# Leds.net
KiCad netlist of a schematic drawn in Altium Designer
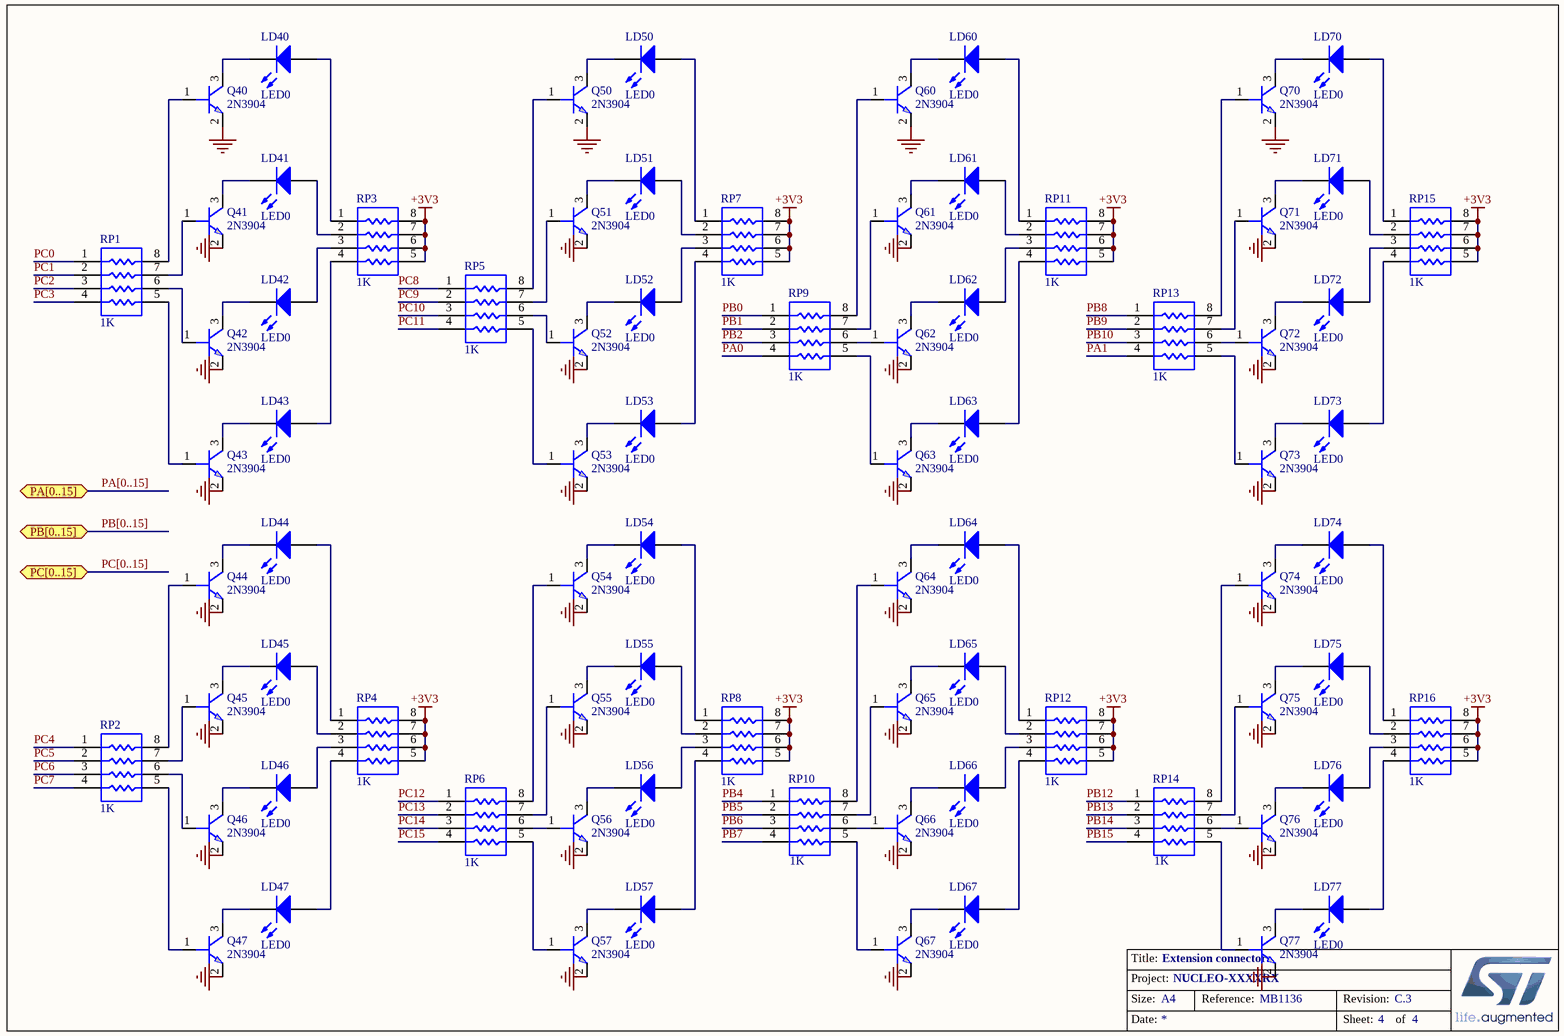
[diagram p0: Leds.SchDoc]

(export (version "E")
  (design (tool "Eeschema 10.0.6"))
  (components
    (comp (ref "LD40")
      (value "LED0")
      (footprint "LED5")
      (description "Typical INFRARED GaAs LED")
      (fields (field (name "PUBLISHER") "Altium Limited"))
      (libsource (lib "Miscellaneous Devices") (part "LED0"))
    )
    (comp (ref "LD41")
      (value "LED0")
      (footprint "LED5")
      (description "Typical INFRARED GaAs LED")
      (fields (field (name "PUBLISHER") "Altium Limited"))
      (libsource (lib "Miscellaneous Devices") (part "LED0"))
    )
    (comp (ref "LD42")
      (value "LED0")
      (footprint "LED5")
      (description "Typical INFRARED GaAs LED")
      (fields (field (name "PUBLISHER") "Altium Limited"))
      (libsource (lib "Miscellaneous Devices") (part "LED0"))
    )
    (comp (ref "LD43")
      (value "LED0")
      (footprint "LED5")
      (description "Typical INFRARED GaAs LED")
      (fields (field (name "PUBLISHER") "Altium Limited"))
      (libsource (lib "Miscellaneous Devices") (part "LED0"))
    )
    (comp (ref "LD44")
      (value "LED0")
      (footprint "LED5")
      (description "Typical INFRARED GaAs LED")
      (fields (field (name "PUBLISHER") "Altium Limited"))
      (libsource (lib "Miscellaneous Devices") (part "LED0"))
    )
    (comp (ref "LD45")
      (value "LED0")
      (footprint "LED5")
      (description "Typical INFRARED GaAs LED")
      (fields (field (name "PUBLISHER") "Altium Limited"))
      (libsource (lib "Miscellaneous Devices") (part "LED0"))
    )
    (comp (ref "LD46")
      (value "LED0")
      (footprint "LED5")
      (description "Typical INFRARED GaAs LED")
      (fields (field (name "PUBLISHER") "Altium Limited"))
      (libsource (lib "Miscellaneous Devices") (part "LED0"))
    )
    (comp (ref "LD47")
      (value "LED0")
      (footprint "LED5")
      (description "Typical INFRARED GaAs LED")
      (fields (field (name "PUBLISHER") "Altium Limited"))
      (libsource (lib "Miscellaneous Devices") (part "LED0"))
    )
    (comp (ref "LD50")
      (value "LED0")
      (footprint "LED5")
      (description "Typical INFRARED GaAs LED")
      (fields (field (name "PUBLISHER") "Altium Limited"))
      (libsource (lib "Miscellaneous Devices") (part "LED0"))
    )
    (comp (ref "LD51")
      (value "LED0")
      (footprint "LED5")
      (description "Typical INFRARED GaAs LED")
      (fields (field (name "PUBLISHER") "Altium Limited"))
      (libsource (lib "Miscellaneous Devices") (part "LED0"))
    )
    (comp (ref "LD52")
      (value "LED0")
      (footprint "LED5")
      (description "Typical INFRARED GaAs LED")
      (fields (field (name "PUBLISHER") "Altium Limited"))
      (libsource (lib "Miscellaneous Devices") (part "LED0"))
    )
    (comp (ref "LD53")
      (value "LED0")
      (footprint "LED5")
      (description "Typical INFRARED GaAs LED")
      (fields (field (name "PUBLISHER") "Altium Limited"))
      (libsource (lib "Miscellaneous Devices") (part "LED0"))
    )
    (comp (ref "LD54")
      (value "LED0")
      (footprint "LED5")
      (description "Typical INFRARED GaAs LED")
      (fields (field (name "PUBLISHER") "Altium Limited"))
      (libsource (lib "Miscellaneous Devices") (part "LED0"))
    )
    (comp (ref "LD55")
      (value "LED0")
      (footprint "LED5")
      (description "Typical INFRARED GaAs LED")
      (fields (field (name "PUBLISHER") "Altium Limited"))
      (libsource (lib "Miscellaneous Devices") (part "LED0"))
    )
    (comp (ref "LD56")
      (value "LED0")
      (footprint "LED5")
      (description "Typical INFRARED GaAs LED")
      (fields (field (name "PUBLISHER") "Altium Limited"))
      (libsource (lib "Miscellaneous Devices") (part "LED0"))
    )
    (comp (ref "LD57")
      (value "LED0")
      (footprint "LED5")
      (description "Typical INFRARED GaAs LED")
      (fields (field (name "PUBLISHER") "Altium Limited"))
      (libsource (lib "Miscellaneous Devices") (part "LED0"))
    )
    (comp (ref "LD60")
      (value "LED0")
      (footprint "LED5")
      (description "Typical INFRARED GaAs LED")
      (fields (field (name "PUBLISHER") "Altium Limited"))
      (libsource (lib "Miscellaneous Devices") (part "LED0"))
    )
    (comp (ref "LD61")
      (value "LED0")
      (footprint "LED5")
      (description "Typical INFRARED GaAs LED")
      (fields (field (name "PUBLISHER") "Altium Limited"))
      (libsource (lib "Miscellaneous Devices") (part "LED0"))
    )
    (comp (ref "LD62")
      (value "LED0")
      (footprint "LED5")
      (description "Typical INFRARED GaAs LED")
      (fields (field (name "PUBLISHER") "Altium Limited"))
      (libsource (lib "Miscellaneous Devices") (part "LED0"))
    )
    (comp (ref "LD63")
      (value "LED0")
      (footprint "LED5")
      (description "Typical INFRARED GaAs LED")
      (fields (field (name "PUBLISHER") "Altium Limited"))
      (libsource (lib "Miscellaneous Devices") (part "LED0"))
    )
    (comp (ref "LD64")
      (value "LED0")
      (footprint "LED5")
      (description "Typical INFRARED GaAs LED")
      (fields (field (name "PUBLISHER") "Altium Limited"))
      (libsource (lib "Miscellaneous Devices") (part "LED0"))
    )
    (comp (ref "LD65")
      (value "LED0")
      (footprint "LED5")
      (description "Typical INFRARED GaAs LED")
      (fields (field (name "PUBLISHER") "Altium Limited"))
      (libsource (lib "Miscellaneous Devices") (part "LED0"))
    )
    (comp (ref "LD66")
      (value "LED0")
      (footprint "LED5")
      (description "Typical INFRARED GaAs LED")
      (fields (field (name "PUBLISHER") "Altium Limited"))
      (libsource (lib "Miscellaneous Devices") (part "LED0"))
    )
    (comp (ref "LD67")
      (value "LED0")
      (footprint "LED5")
      (description "Typical INFRARED GaAs LED")
      (fields (field (name "PUBLISHER") "Altium Limited"))
      (libsource (lib "Miscellaneous Devices") (part "LED0"))
    )
    (comp (ref "LD70")
      (value "LED0")
      (footprint "LED5")
      (description "Typical INFRARED GaAs LED")
      (fields (field (name "PUBLISHER") "Altium Limited"))
      (libsource (lib "Miscellaneous Devices") (part "LED0"))
    )
    (comp (ref "LD71")
      (value "LED0")
      (footprint "LED5")
      (description "Typical INFRARED GaAs LED")
      (fields (field (name "PUBLISHER") "Altium Limited"))
      (libsource (lib "Miscellaneous Devices") (part "LED0"))
    )
    (comp (ref "LD72")
      (value "LED0")
      (footprint "LED5")
      (description "Typical INFRARED GaAs LED")
      (fields (field (name "PUBLISHER") "Altium Limited"))
      (libsource (lib "Miscellaneous Devices") (part "LED0"))
    )
    (comp (ref "LD73")
      (value "LED0")
      (footprint "LED5")
      (description "Typical INFRARED GaAs LED")
      (fields (field (name "PUBLISHER") "Altium Limited"))
      (libsource (lib "Miscellaneous Devices") (part "LED0"))
    )
    (comp (ref "LD74")
      (value "LED0")
      (footprint "LED5")
      (description "Typical INFRARED GaAs LED")
      (fields (field (name "PUBLISHER") "Altium Limited"))
      (libsource (lib "Miscellaneous Devices") (part "LED0"))
    )
    (comp (ref "LD75")
      (value "LED0")
      (footprint "LED5")
      (description "Typical INFRARED GaAs LED")
      (fields (field (name "PUBLISHER") "Altium Limited"))
      (libsource (lib "Miscellaneous Devices") (part "LED0"))
    )
    (comp (ref "LD76")
      (value "LED0")
      (footprint "LED5")
      (description "Typical INFRARED GaAs LED")
      (fields (field (name "PUBLISHER") "Altium Limited"))
      (libsource (lib "Miscellaneous Devices") (part "LED0"))
    )
    (comp (ref "LD77")
      (value "LED0")
      (footprint "LED5")
      (description "Typical INFRARED GaAs LED")
      (fields (field (name "PUBLISHER") "Altium Limited"))
      (libsource (lib "Miscellaneous Devices") (part "LED0"))
    )
    (comp (ref "Q40") (value "2N3904") (footprint "SOT-23") (libsource (lib "*") (part "2N5551")))
    (comp (ref "Q41") (value "2N3904") (footprint "SOT-23") (libsource (lib "*") (part "2N5551")))
    (comp (ref "Q42") (value "2N3904") (footprint "SOT-23") (libsource (lib "*") (part "2N5551")))
    (comp (ref "Q43") (value "2N3904") (footprint "SOT-23") (libsource (lib "*") (part "2N5551")))
    (comp (ref "Q44") (value "2N3904") (footprint "SOT-23") (libsource (lib "*") (part "2N5551")))
    (comp (ref "Q45") (value "2N3904") (footprint "SOT-23") (libsource (lib "*") (part "2N5551")))
    (comp (ref "Q46") (value "2N3904") (footprint "SOT-23") (libsource (lib "*") (part "2N5551")))
    (comp (ref "Q47") (value "2N3904") (footprint "SOT-23") (libsource (lib "*") (part "2N5551")))
    (comp (ref "Q50") (value "2N3904") (footprint "SOT-23") (libsource (lib "*") (part "2N5551")))
    (comp (ref "Q51") (value "2N3904") (footprint "SOT-23") (libsource (lib "*") (part "2N5551")))
    (comp (ref "Q52") (value "2N3904") (footprint "SOT-23") (libsource (lib "*") (part "2N5551")))
    (comp (ref "Q53") (value "2N3904") (footprint "SOT-23") (libsource (lib "*") (part "2N5551")))
    (comp (ref "Q54") (value "2N3904") (footprint "SOT-23") (libsource (lib "*") (part "2N5551")))
    (comp (ref "Q55") (value "2N3904") (footprint "SOT-23") (libsource (lib "*") (part "2N5551")))
    (comp (ref "Q56") (value "2N3904") (footprint "SOT-23") (libsource (lib "*") (part "2N5551")))
    (comp (ref "Q57") (value "2N3904") (footprint "SOT-23") (libsource (lib "*") (part "2N5551")))
    (comp (ref "Q60") (value "2N3904") (footprint "SOT-23") (libsource (lib "*") (part "2N5551")))
    (comp (ref "Q61") (value "2N3904") (footprint "SOT-23") (libsource (lib "*") (part "2N5551")))
    (comp (ref "Q62") (value "2N3904") (footprint "SOT-23") (libsource (lib "*") (part "2N5551")))
    (comp (ref "Q63") (value "2N3904") (footprint "SOT-23") (libsource (lib "*") (part "2N5551")))
    (comp (ref "Q64") (value "2N3904") (footprint "SOT-23") (libsource (lib "*") (part "2N5551")))
    (comp (ref "Q65") (value "2N3904") (footprint "SOT-23") (libsource (lib "*") (part "2N5551")))
    (comp (ref "Q66") (value "2N3904") (footprint "SOT-23") (libsource (lib "*") (part "2N5551")))
    (comp (ref "Q67") (value "2N3904") (footprint "SOT-23") (libsource (lib "*") (part "2N5551")))
    (comp (ref "Q70") (value "2N3904") (footprint "SOT-23") (libsource (lib "*") (part "2N5551")))
    (comp (ref "Q71") (value "2N3904") (footprint "SOT-23") (libsource (lib "*") (part "2N5551")))
    (comp (ref "Q72") (value "2N3904") (footprint "SOT-23") (libsource (lib "*") (part "2N5551")))
    (comp (ref "Q73") (value "2N3904") (footprint "SOT-23") (libsource (lib "*") (part "2N5551")))
    (comp (ref "Q74") (value "2N3904") (footprint "SOT-23") (libsource (lib "*") (part "2N5551")))
    (comp (ref "Q75") (value "2N3904") (footprint "SOT-23") (libsource (lib "*") (part "2N5551")))
    (comp (ref "Q76") (value "2N3904") (footprint "SOT-23") (libsource (lib "*") (part "2N5551")))
    (comp (ref "Q77") (value "2N3904") (footprint "SOT-23") (libsource (lib "*") (part "2N5551")))
    (comp (ref "RP1") (value "1K") (footprint "4P8") (libsource (lib "*") (part "RESPACK3_1")))
    (comp (ref "RP2") (value "1K") (footprint "4P8") (libsource (lib "*") (part "RESPACK3_1")))
    (comp (ref "RP3") (value "1K") (footprint "4P8") (libsource (lib "*") (part "RESPACK3_1")))
    (comp (ref "RP4") (value "1K") (footprint "4P8") (libsource (lib "*") (part "RESPACK3_1")))
    (comp (ref "RP5") (value "1K") (footprint "4P8") (libsource (lib "*") (part "RESPACK3_1")))
    (comp (ref "RP6") (value "1K") (footprint "4P8") (libsource (lib "*") (part "RESPACK3_1")))
    (comp (ref "RP7") (value "1K") (footprint "4P8") (libsource (lib "*") (part "RESPACK3_1")))
    (comp (ref "RP8") (value "1K") (footprint "4P8") (libsource (lib "*") (part "RESPACK3_1")))
    (comp (ref "RP9") (value "1K") (footprint "4P8") (libsource (lib "*") (part "RESPACK3_1")))
    (comp (ref "RP10") (value "1K") (footprint "4P8") (libsource (lib "*") (part "RESPACK3_1")))
    (comp (ref "RP11") (value "1K") (footprint "4P8") (libsource (lib "*") (part "RESPACK3_1")))
    (comp (ref "RP12") (value "1K") (footprint "4P8") (libsource (lib "*") (part "RESPACK3_1")))
    (comp (ref "RP13") (value "1K") (footprint "4P8") (libsource (lib "*") (part "RESPACK3_1")))
    (comp (ref "RP14") (value "1K") (footprint "4P8") (libsource (lib "*") (part "RESPACK3_1")))
    (comp (ref "RP15") (value "1K") (footprint "4P8") (libsource (lib "*") (part "RESPACK3_1")))
    (comp (ref "RP16") (value "1K") (footprint "4P8") (libsource (lib "*") (part "RESPACK3_1")))
  )
  (nets
    (net (code "17") (name "+3V3") (class "Default")
      (node (ref "RP11") (pin "5") (pinfunction "5_5") (pintype "passive"))
      (node (ref "RP11") (pin "6") (pinfunction "6_6") (pintype "passive"))
      (node (ref "RP11") (pin "7") (pinfunction "7_7") (pintype "passive"))
      (node (ref "RP11") (pin "8") (pinfunction "8_8") (pintype "passive"))
      (node (ref "RP12") (pin "5") (pinfunction "5_5") (pintype "passive"))
      (node (ref "RP12") (pin "6") (pinfunction "6_6") (pintype "passive"))
      (node (ref "RP12") (pin "7") (pinfunction "7_7") (pintype "passive"))
      (node (ref "RP12") (pin "8") (pinfunction "8_8") (pintype "passive"))
      (node (ref "RP15") (pin "5") (pinfunction "5_5") (pintype "passive"))
      (node (ref "RP15") (pin "6") (pinfunction "6_6") (pintype "passive"))
      (node (ref "RP15") (pin "7") (pinfunction "7_7") (pintype "passive"))
      (node (ref "RP15") (pin "8") (pinfunction "8_8") (pintype "passive"))
      (node (ref "RP16") (pin "5") (pinfunction "5_5") (pintype "passive"))
      (node (ref "RP16") (pin "6") (pinfunction "6_6") (pintype "passive"))
      (node (ref "RP16") (pin "7") (pinfunction "7_7") (pintype "passive"))
      (node (ref "RP16") (pin "8") (pinfunction "8_8") (pintype "passive"))
      (node (ref "RP3") (pin "5") (pinfunction "5_5") (pintype "passive"))
      (node (ref "RP3") (pin "6") (pinfunction "6_6") (pintype "passive"))
      (node (ref "RP3") (pin "7") (pinfunction "7_7") (pintype "passive"))
      (node (ref "RP3") (pin "8") (pinfunction "8_8") (pintype "passive"))
      (node (ref "RP4") (pin "5") (pinfunction "5_5") (pintype "passive"))
      (node (ref "RP4") (pin "6") (pinfunction "6_6") (pintype "passive"))
      (node (ref "RP4") (pin "7") (pinfunction "7_7") (pintype "passive"))
      (node (ref "RP4") (pin "8") (pinfunction "8_8") (pintype "passive"))
      (node (ref "RP7") (pin "5") (pinfunction "5_5") (pintype "passive"))
      (node (ref "RP7") (pin "6") (pinfunction "6_6") (pintype "passive"))
      (node (ref "RP7") (pin "7") (pinfunction "7_7") (pintype "passive"))
      (node (ref "RP7") (pin "8") (pinfunction "8_8") (pintype "passive"))
      (node (ref "RP8") (pin "5") (pinfunction "5_5") (pintype "passive"))
      (node (ref "RP8") (pin "6") (pinfunction "6_6") (pintype "passive"))
      (node (ref "RP8") (pin "7") (pinfunction "7_7") (pintype "passive"))
      (node (ref "RP8") (pin "8") (pinfunction "8_8") (pintype "passive"))
    )
    (net (code "18") (name "/PA0") (class "Default")
      (node (ref "RP9") (pin "4") (pinfunction "4_4") (pintype "passive"))
    )
    (net (code "19") (name "/PA1") (class "Default")
      (node (ref "RP13") (pin "4") (pinfunction "4_4") (pintype "passive"))
    )
    (net (code "21") (name "/PB0") (class "Default")
      (node (ref "RP9") (pin "1") (pinfunction "1_1") (pintype "passive"))
    )
    (net (code "22") (name "/PB1") (class "Default")
      (node (ref "RP9") (pin "2") (pinfunction "2_2") (pintype "passive"))
    )
    (net (code "23") (name "/PB2") (class "Default")
      (node (ref "RP9") (pin "3") (pinfunction "3_3") (pintype "passive"))
    )
    (net (code "24") (name "/PB4") (class "Default")
      (node (ref "RP10") (pin "1") (pinfunction "1_1") (pintype "passive"))
    )
    (net (code "25") (name "/PB5") (class "Default")
      (node (ref "RP10") (pin "2") (pinfunction "2_2") (pintype "passive"))
    )
    (net (code "26") (name "/PB6") (class "Default")
      (node (ref "RP10") (pin "3") (pinfunction "3_3") (pintype "passive"))
    )
    (net (code "27") (name "/PB7") (class "Default")
      (node (ref "RP10") (pin "4") (pinfunction "4_4") (pintype "passive"))
    )
    (net (code "28") (name "/PB8") (class "Default")
      (node (ref "RP13") (pin "1") (pinfunction "1_1") (pintype "passive"))
    )
    (net (code "29") (name "/PB9") (class "Default")
      (node (ref "RP13") (pin "2") (pinfunction "2_2") (pintype "passive"))
    )
    (net (code "30") (name "/PB10") (class "Default")
      (node (ref "RP13") (pin "3") (pinfunction "3_3") (pintype "passive"))
    )
    (net (code "31") (name "/PB12") (class "Default")
      (node (ref "RP14") (pin "1") (pinfunction "1_1") (pintype "passive"))
    )
    (net (code "32") (name "/PB13") (class "Default")
      (node (ref "RP14") (pin "2") (pinfunction "2_2") (pintype "passive"))
    )
    (net (code "33") (name "/PB14") (class "Default")
      (node (ref "RP14") (pin "3") (pinfunction "3_3") (pintype "passive"))
    )
    (net (code "34") (name "/PB15") (class "Default")
      (node (ref "RP14") (pin "4") (pinfunction "4_4") (pintype "passive"))
    )
    (net (code "36") (name "/PC0") (class "Default")
      (node (ref "RP1") (pin "1") (pinfunction "1_1") (pintype "passive"))
    )
    (net (code "37") (name "/PC1") (class "Default")
      (node (ref "RP1") (pin "2") (pinfunction "2_2") (pintype "passive"))
    )
    (net (code "38") (name "/PC2") (class "Default")
      (node (ref "RP1") (pin "3") (pinfunction "3_3") (pintype "passive"))
    )
    (net (code "39") (name "/PC3") (class "Default")
      (node (ref "RP1") (pin "4") (pinfunction "4_4") (pintype "passive"))
    )
    (net (code "40") (name "/PC4") (class "Default")
      (node (ref "RP2") (pin "1") (pinfunction "1_1") (pintype "passive"))
    )
    (net (code "41") (name "/PC5") (class "Default")
      (node (ref "RP2") (pin "2") (pinfunction "2_2") (pintype "passive"))
    )
    (net (code "42") (name "/PC6") (class "Default")
      (node (ref "RP2") (pin "3") (pinfunction "3_3") (pintype "passive"))
    )
    (net (code "43") (name "/PC7") (class "Default")
      (node (ref "RP2") (pin "4") (pinfunction "4_4") (pintype "passive"))
    )
    (net (code "44") (name "/PC8") (class "Default")
      (node (ref "RP5") (pin "1") (pinfunction "1_1") (pintype "passive"))
    )
    (net (code "45") (name "/PC9") (class "Default")
      (node (ref "RP5") (pin "2") (pinfunction "2_2") (pintype "passive"))
    )
    (net (code "46") (name "/PC10") (class "Default")
      (node (ref "RP5") (pin "3") (pinfunction "3_3") (pintype "passive"))
    )
    (net (code "47") (name "/PC11") (class "Default")
      (node (ref "RP5") (pin "4") (pinfunction "4_4") (pintype "passive"))
    )
    (net (code "48") (name "/PC12") (class "Default")
      (node (ref "RP6") (pin "1") (pinfunction "1_1") (pintype "passive"))
    )
    (net (code "49") (name "/PC13") (class "Default")
      (node (ref "RP6") (pin "2") (pinfunction "2_2") (pintype "passive"))
    )
    (net (code "50") (name "/PC14") (class "Default")
      (node (ref "RP6") (pin "3") (pinfunction "3_3") (pintype "passive"))
    )
    (net (code "51") (name "/PC15") (class "Default")
      (node (ref "RP6") (pin "4") (pinfunction "4_4") (pintype "passive"))
    )
    (net (code "53") (name "GND") (class "Default")
      (node (ref "Q40") (pin "2") (pinfunction "E_2") (pintype "passive"))
      (node (ref "Q41") (pin "2") (pinfunction "E_2") (pintype "passive"))
      (node (ref "Q42") (pin "2") (pinfunction "E_2") (pintype "passive"))
      (node (ref "Q43") (pin "2") (pinfunction "E_2") (pintype "passive"))
      (node (ref "Q44") (pin "2") (pinfunction "E_2") (pintype "passive"))
      (node (ref "Q45") (pin "2") (pinfunction "E_2") (pintype "passive"))
      (node (ref "Q46") (pin "2") (pinfunction "E_2") (pintype "passive"))
      (node (ref "Q47") (pin "2") (pinfunction "E_2") (pintype "passive"))
      (node (ref "Q50") (pin "2") (pinfunction "E_2") (pintype "passive"))
      (node (ref "Q51") (pin "2") (pinfunction "E_2") (pintype "passive"))
      (node (ref "Q52") (pin "2") (pinfunction "E_2") (pintype "passive"))
      (node (ref "Q53") (pin "2") (pinfunction "E_2") (pintype "passive"))
      (node (ref "Q54") (pin "2") (pinfunction "E_2") (pintype "passive"))
      (node (ref "Q55") (pin "2") (pinfunction "E_2") (pintype "passive"))
      (node (ref "Q56") (pin "2") (pinfunction "E_2") (pintype "passive"))
      (node (ref "Q57") (pin "2") (pinfunction "E_2") (pintype "passive"))
      (node (ref "Q60") (pin "2") (pinfunction "E_2") (pintype "passive"))
      (node (ref "Q61") (pin "2") (pinfunction "E_2") (pintype "passive"))
      (node (ref "Q62") (pin "2") (pinfunction "E_2") (pintype "passive"))
      (node (ref "Q63") (pin "2") (pinfunction "E_2") (pintype "passive"))
      (node (ref "Q64") (pin "2") (pinfunction "E_2") (pintype "passive"))
      (node (ref "Q65") (pin "2") (pinfunction "E_2") (pintype "passive"))
      (node (ref "Q66") (pin "2") (pinfunction "E_2") (pintype "passive"))
      (node (ref "Q67") (pin "2") (pinfunction "E_2") (pintype "passive"))
      (node (ref "Q70") (pin "2") (pinfunction "E_2") (pintype "passive"))
      (node (ref "Q71") (pin "2") (pinfunction "E_2") (pintype "passive"))
      (node (ref "Q72") (pin "2") (pinfunction "E_2") (pintype "passive"))
      (node (ref "Q73") (pin "2") (pinfunction "E_2") (pintype "passive"))
      (node (ref "Q74") (pin "2") (pinfunction "E_2") (pintype "passive"))
      (node (ref "Q75") (pin "2") (pinfunction "E_2") (pintype "passive"))
      (node (ref "Q76") (pin "2") (pinfunction "E_2") (pintype "passive"))
      (node (ref "Q77") (pin "2") (pinfunction "E_2") (pintype "passive"))
    )
    (net (code "54") (name "Net-(LD40-A)") (class "Default")
      (node (ref "LD40") (pin "1") (pinfunction "A_1") (pintype "passive"))
      (node (ref "RP3") (pin "1") (pinfunction "1_1") (pintype "passive"))
    )
    (net (code "55") (name "Net-(LD40-K)") (class "Default")
      (node (ref "LD40") (pin "2") (pinfunction "K_2") (pintype "passive"))
      (node (ref "Q40") (pin "3") (pinfunction "C_3") (pintype "passive"))
    )
    (net (code "56") (name "Net-(LD41-A)") (class "Default")
      (node (ref "LD41") (pin "1") (pinfunction "A_1") (pintype "passive"))
      (node (ref "RP3") (pin "2") (pinfunction "2_2") (pintype "passive"))
    )
    (net (code "57") (name "Net-(LD41-K)") (class "Default")
      (node (ref "LD41") (pin "2") (pinfunction "K_2") (pintype "passive"))
      (node (ref "Q41") (pin "3") (pinfunction "C_3") (pintype "passive"))
    )
    (net (code "58") (name "Net-(LD42-A)") (class "Default")
      (node (ref "LD42") (pin "1") (pinfunction "A_1") (pintype "passive"))
      (node (ref "RP3") (pin "3") (pinfunction "3_3") (pintype "passive"))
    )
    (net (code "59") (name "Net-(LD42-K)") (class "Default")
      (node (ref "LD42") (pin "2") (pinfunction "K_2") (pintype "passive"))
      (node (ref "Q42") (pin "3") (pinfunction "C_3") (pintype "passive"))
    )
    (net (code "60") (name "Net-(LD43-A)") (class "Default")
      (node (ref "LD43") (pin "1") (pinfunction "A_1") (pintype "passive"))
      (node (ref "RP3") (pin "4") (pinfunction "4_4") (pintype "passive"))
    )
    (net (code "61") (name "Net-(LD43-K)") (class "Default")
      (node (ref "LD43") (pin "2") (pinfunction "K_2") (pintype "passive"))
      (node (ref "Q43") (pin "3") (pinfunction "C_3") (pintype "passive"))
    )
    (net (code "62") (name "Net-(LD44-A)") (class "Default")
      (node (ref "LD44") (pin "1") (pinfunction "A_1") (pintype "passive"))
      (node (ref "RP4") (pin "1") (pinfunction "1_1") (pintype "passive"))
    )
    (net (code "63") (name "Net-(LD44-K)") (class "Default")
      (node (ref "LD44") (pin "2") (pinfunction "K_2") (pintype "passive"))
      (node (ref "Q44") (pin "3") (pinfunction "C_3") (pintype "passive"))
    )
    (net (code "64") (name "Net-(LD45-A)") (class "Default")
      (node (ref "LD45") (pin "1") (pinfunction "A_1") (pintype "passive"))
      (node (ref "RP4") (pin "2") (pinfunction "2_2") (pintype "passive"))
    )
    (net (code "65") (name "Net-(LD45-K)") (class "Default")
      (node (ref "LD45") (pin "2") (pinfunction "K_2") (pintype "passive"))
      (node (ref "Q45") (pin "3") (pinfunction "C_3") (pintype "passive"))
    )
    (net (code "66") (name "Net-(LD46-A)") (class "Default")
      (node (ref "LD46") (pin "1") (pinfunction "A_1") (pintype "passive"))
      (node (ref "RP4") (pin "3") (pinfunction "3_3") (pintype "passive"))
    )
    (net (code "67") (name "Net-(LD46-K)") (class "Default")
      (node (ref "LD46") (pin "2") (pinfunction "K_2") (pintype "passive"))
      (node (ref "Q46") (pin "3") (pinfunction "C_3") (pintype "passive"))
    )
    (net (code "68") (name "Net-(LD47-A)") (class "Default")
      (node (ref "LD47") (pin "1") (pinfunction "A_1") (pintype "passive"))
      (node (ref "RP4") (pin "4") (pinfunction "4_4") (pintype "passive"))
    )
    (net (code "69") (name "Net-(LD47-K)") (class "Default")
      (node (ref "LD47") (pin "2") (pinfunction "K_2") (pintype "passive"))
      (node (ref "Q47") (pin "3") (pinfunction "C_3") (pintype "passive"))
    )
    (net (code "70") (name "Net-(LD50-A)") (class "Default")
      (node (ref "LD50") (pin "1") (pinfunction "A_1") (pintype "passive"))
      (node (ref "RP7") (pin "1") (pinfunction "1_1") (pintype "passive"))
    )
    (net (code "71") (name "Net-(LD50-K)") (class "Default")
      (node (ref "LD50") (pin "2") (pinfunction "K_2") (pintype "passive"))
      (node (ref "Q50") (pin "3") (pinfunction "C_3") (pintype "passive"))
    )
    (net (code "72") (name "Net-(LD51-A)") (class "Default")
      (node (ref "LD51") (pin "1") (pinfunction "A_1") (pintype "passive"))
      (node (ref "RP7") (pin "2") (pinfunction "2_2") (pintype "passive"))
    )
    (net (code "73") (name "Net-(LD51-K)") (class "Default")
      (node (ref "LD51") (pin "2") (pinfunction "K_2") (pintype "passive"))
      (node (ref "Q51") (pin "3") (pinfunction "C_3") (pintype "passive"))
    )
    (net (code "74") (name "Net-(LD52-A)") (class "Default")
      (node (ref "LD52") (pin "1") (pinfunction "A_1") (pintype "passive"))
      (node (ref "RP7") (pin "3") (pinfunction "3_3") (pintype "passive"))
    )
    (net (code "75") (name "Net-(LD52-K)") (class "Default")
      (node (ref "LD52") (pin "2") (pinfunction "K_2") (pintype "passive"))
      (node (ref "Q52") (pin "3") (pinfunction "C_3") (pintype "passive"))
    )
    (net (code "76") (name "Net-(LD53-A)") (class "Default")
      (node (ref "LD53") (pin "1") (pinfunction "A_1") (pintype "passive"))
      (node (ref "RP7") (pin "4") (pinfunction "4_4") (pintype "passive"))
    )
    (net (code "77") (name "Net-(LD53-K)") (class "Default")
      (node (ref "LD53") (pin "2") (pinfunction "K_2") (pintype "passive"))
      (node (ref "Q53") (pin "3") (pinfunction "C_3") (pintype "passive"))
    )
    (net (code "78") (name "Net-(LD54-A)") (class "Default")
      (node (ref "LD54") (pin "1") (pinfunction "A_1") (pintype "passive"))
      (node (ref "RP8") (pin "1") (pinfunction "1_1") (pintype "passive"))
    )
    (net (code "79") (name "Net-(LD54-K)") (class "Default")
      (node (ref "LD54") (pin "2") (pinfunction "K_2") (pintype "passive"))
      (node (ref "Q54") (pin "3") (pinfunction "C_3") (pintype "passive"))
    )
    (net (code "80") (name "Net-(LD55-A)") (class "Default")
      (node (ref "LD55") (pin "1") (pinfunction "A_1") (pintype "passive"))
      (node (ref "RP8") (pin "2") (pinfunction "2_2") (pintype "passive"))
    )
    (net (code "81") (name "Net-(LD55-K)") (class "Default")
      (node (ref "LD55") (pin "2") (pinfunction "K_2") (pintype "passive"))
      (node (ref "Q55") (pin "3") (pinfunction "C_3") (pintype "passive"))
    )
    (net (code "82") (name "Net-(LD56-A)") (class "Default")
      (node (ref "LD56") (pin "1") (pinfunction "A_1") (pintype "passive"))
      (node (ref "RP8") (pin "3") (pinfunction "3_3") (pintype "passive"))
    )
    (net (code "83") (name "Net-(LD56-K)") (class "Default")
      (node (ref "LD56") (pin "2") (pinfunction "K_2") (pintype "passive"))
      (node (ref "Q56") (pin "3") (pinfunction "C_3") (pintype "passive"))
    )
    (net (code "84") (name "Net-(LD57-A)") (class "Default")
      (node (ref "LD57") (pin "1") (pinfunction "A_1") (pintype "passive"))
      (node (ref "RP8") (pin "4") (pinfunction "4_4") (pintype "passive"))
    )
    (net (code "85") (name "Net-(LD57-K)") (class "Default")
      (node (ref "LD57") (pin "2") (pinfunction "K_2") (pintype "passive"))
      (node (ref "Q57") (pin "3") (pinfunction "C_3") (pintype "passive"))
    )
    (net (code "86") (name "Net-(LD60-A)") (class "Default")
      (node (ref "LD60") (pin "1") (pinfunction "A_1") (pintype "passive"))
      (node (ref "RP11") (pin "1") (pinfunction "1_1") (pintype "passive"))
    )
    (net (code "87") (name "Net-(LD60-K)") (class "Default")
      (node (ref "LD60") (pin "2") (pinfunction "K_2") (pintype "passive"))
      (node (ref "Q60") (pin "3") (pinfunction "C_3") (pintype "passive"))
    )
    (net (code "88") (name "Net-(LD61-A)") (class "Default")
      (node (ref "LD61") (pin "1") (pinfunction "A_1") (pintype "passive"))
      (node (ref "RP11") (pin "2") (pinfunction "2_2") (pintype "passive"))
    )
    (net (code "89") (name "Net-(LD61-K)") (class "Default")
      (node (ref "LD61") (pin "2") (pinfunction "K_2") (pintype "passive"))
      (node (ref "Q61") (pin "3") (pinfunction "C_3") (pintype "passive"))
    )
    (net (code "90") (name "Net-(LD62-A)") (class "Default")
      (node (ref "LD62") (pin "1") (pinfunction "A_1") (pintype "passive"))
      (node (ref "RP11") (pin "3") (pinfunction "3_3") (pintype "passive"))
    )
    (net (code "91") (name "Net-(LD62-K)") (class "Default")
      (node (ref "LD62") (pin "2") (pinfunction "K_2") (pintype "passive"))
      (node (ref "Q62") (pin "3") (pinfunction "C_3") (pintype "passive"))
    )
    (net (code "92") (name "Net-(LD63-A)") (class "Default")
      (node (ref "LD63") (pin "1") (pinfunction "A_1") (pintype "passive"))
      (node (ref "RP11") (pin "4") (pinfunction "4_4") (pintype "passive"))
    )
    (net (code "93") (name "Net-(LD63-K)") (class "Default")
      (node (ref "LD63") (pin "2") (pinfunction "K_2") (pintype "passive"))
      (node (ref "Q63") (pin "3") (pinfunction "C_3") (pintype "passive"))
    )
    (net (code "94") (name "Net-(LD64-A)") (class "Default")
      (node (ref "LD64") (pin "1") (pinfunction "A_1") (pintype "passive"))
      (node (ref "RP12") (pin "1") (pinfunction "1_1") (pintype "passive"))
    )
    (net (code "95") (name "Net-(LD64-K)") (class "Default")
      (node (ref "LD64") (pin "2") (pinfunction "K_2") (pintype "passive"))
      (node (ref "Q64") (pin "3") (pinfunction "C_3") (pintype "passive"))
    )
    (net (code "96") (name "Net-(LD65-A)") (class "Default")
      (node (ref "LD65") (pin "1") (pinfunction "A_1") (pintype "passive"))
      (node (ref "RP12") (pin "2") (pinfunction "2_2") (pintype "passive"))
    )
    (net (code "97") (name "Net-(LD65-K)") (class "Default")
      (node (ref "LD65") (pin "2") (pinfunction "K_2") (pintype "passive"))
      (node (ref "Q65") (pin "3") (pinfunction "C_3") (pintype "passive"))
    )
    (net (code "98") (name "Net-(LD66-A)") (class "Default")
      (node (ref "LD66") (pin "1") (pinfunction "A_1") (pintype "passive"))
      (node (ref "RP12") (pin "3") (pinfunction "3_3") (pintype "passive"))
    )
    (net (code "99") (name "Net-(LD66-K)") (class "Default")
      (node (ref "LD66") (pin "2") (pinfunction "K_2") (pintype "passive"))
      (node (ref "Q66") (pin "3") (pinfunction "C_3") (pintype "passive"))
    )
    (net (code "100") (name "Net-(LD67-A)") (class "Default")
      (node (ref "LD67") (pin "1") (pinfunction "A_1") (pintype "passive"))
      (node (ref "RP12") (pin "4") (pinfunction "4_4") (pintype "passive"))
    )
    (net (code "101") (name "Net-(LD67-K)") (class "Default")
      (node (ref "LD67") (pin "2") (pinfunction "K_2") (pintype "passive"))
      (node (ref "Q67") (pin "3") (pinfunction "C_3") (pintype "passive"))
    )
    (net (code "102") (name "Net-(LD70-A)") (class "Default")
      (node (ref "LD70") (pin "1") (pinfunction "A_1") (pintype "passive"))
      (node (ref "RP15") (pin "1") (pinfunction "1_1") (pintype "passive"))
    )
    (net (code "103") (name "Net-(LD70-K)") (class "Default")
      (node (ref "LD70") (pin "2") (pinfunction "K_2") (pintype "passive"))
      (node (ref "Q70") (pin "3") (pinfunction "C_3") (pintype "passive"))
    )
    (net (code "104") (name "Net-(LD71-A)") (class "Default")
      (node (ref "LD71") (pin "1") (pinfunction "A_1") (pintype "passive"))
      (node (ref "RP15") (pin "2") (pinfunction "2_2") (pintype "passive"))
    )
    (net (code "105") (name "Net-(LD71-K)") (class "Default")
      (node (ref "LD71") (pin "2") (pinfunction "K_2") (pintype "passive"))
      (node (ref "Q71") (pin "3") (pinfunction "C_3") (pintype "passive"))
    )
    (net (code "106") (name "Net-(LD72-A)") (class "Default")
      (node (ref "LD72") (pin "1") (pinfunction "A_1") (pintype "passive"))
      (node (ref "RP15") (pin "3") (pinfunction "3_3") (pintype "passive"))
    )
    (net (code "107") (name "Net-(LD72-K)") (class "Default")
      (node (ref "LD72") (pin "2") (pinfunction "K_2") (pintype "passive"))
      (node (ref "Q72") (pin "3") (pinfunction "C_3") (pintype "passive"))
    )
    (net (code "108") (name "Net-(LD73-A)") (class "Default")
      (node (ref "LD73") (pin "1") (pinfunction "A_1") (pintype "passive"))
      (node (ref "RP15") (pin "4") (pinfunction "4_4") (pintype "passive"))
    )
    (net (code "109") (name "Net-(LD73-K)") (class "Default")
      (node (ref "LD73") (pin "2") (pinfunction "K_2") (pintype "passive"))
      (node (ref "Q73") (pin "3") (pinfunction "C_3") (pintype "passive"))
    )
    (net (code "110") (name "Net-(LD74-A)") (class "Default")
      (node (ref "LD74") (pin "1") (pinfunction "A_1") (pintype "passive"))
      (node (ref "RP16") (pin "1") (pinfunction "1_1") (pintype "passive"))
    )
    (net (code "111") (name "Net-(LD74-K)") (class "Default")
      (node (ref "LD74") (pin "2") (pinfunction "K_2") (pintype "passive"))
      (node (ref "Q74") (pin "3") (pinfunction "C_3") (pintype "passive"))
    )
    (net (code "112") (name "Net-(LD75-A)") (class "Default")
      (node (ref "LD75") (pin "1") (pinfunction "A_1") (pintype "passive"))
      (node (ref "RP16") (pin "2") (pinfunction "2_2") (pintype "passive"))
    )
    (net (code "113") (name "Net-(LD75-K)") (class "Default")
      (node (ref "LD75") (pin "2") (pinfunction "K_2") (pintype "passive"))
      (node (ref "Q75") (pin "3") (pinfunction "C_3") (pintype "passive"))
    )
    (net (code "114") (name "Net-(LD76-A)") (class "Default")
      (node (ref "LD76") (pin "1") (pinfunction "A_1") (pintype "passive"))
      (node (ref "RP16") (pin "3") (pinfunction "3_3") (pintype "passive"))
    )
    (net (code "115") (name "Net-(LD76-K)") (class "Default")
      (node (ref "LD76") (pin "2") (pinfunction "K_2") (pintype "passive"))
      (node (ref "Q76") (pin "3") (pinfunction "C_3") (pintype "passive"))
    )
    (net (code "116") (name "Net-(LD77-A)") (class "Default")
      (node (ref "LD77") (pin "1") (pinfunction "A_1") (pintype "passive"))
      (node (ref "RP16") (pin "4") (pinfunction "4_4") (pintype "passive"))
    )
    (net (code "117") (name "Net-(LD77-K)") (class "Default")
      (node (ref "LD77") (pin "2") (pinfunction "K_2") (pintype "passive"))
      (node (ref "Q77") (pin "3") (pinfunction "C_3") (pintype "passive"))
    )
    (net (code "118") (name "Net-(Q40-B)") (class "Default")
      (node (ref "Q40") (pin "1") (pinfunction "B_1") (pintype "passive"))
      (node (ref "RP1") (pin "8") (pinfunction "8_8") (pintype "passive"))
    )
    (net (code "119") (name "Net-(Q41-B)") (class "Default")
      (node (ref "Q41") (pin "1") (pinfunction "B_1") (pintype "passive"))
      (node (ref "RP1") (pin "7") (pinfunction "7_7") (pintype "passive"))
    )
    (net (code "120") (name "Net-(Q42-B)") (class "Default")
      (node (ref "Q42") (pin "1") (pinfunction "B_1") (pintype "passive"))
      (node (ref "RP1") (pin "6") (pinfunction "6_6") (pintype "passive"))
    )
    (net (code "121") (name "Net-(Q43-B)") (class "Default")
      (node (ref "Q43") (pin "1") (pinfunction "B_1") (pintype "passive"))
      (node (ref "RP1") (pin "5") (pinfunction "5_5") (pintype "passive"))
    )
    (net (code "122") (name "Net-(Q44-B)") (class "Default")
      (node (ref "Q44") (pin "1") (pinfunction "B_1") (pintype "passive"))
      (node (ref "RP2") (pin "8") (pinfunction "8_8") (pintype "passive"))
    )
    (net (code "123") (name "Net-(Q45-B)") (class "Default")
      (node (ref "Q45") (pin "1") (pinfunction "B_1") (pintype "passive"))
      (node (ref "RP2") (pin "7") (pinfunction "7_7") (pintype "passive"))
    )
    (net (code "124") (name "Net-(Q46-B)") (class "Default")
      (node (ref "Q46") (pin "1") (pinfunction "B_1") (pintype "passive"))
      (node (ref "RP2") (pin "6") (pinfunction "6_6") (pintype "passive"))
    )
    (net (code "125") (name "Net-(Q47-B)") (class "Default")
      (node (ref "Q47") (pin "1") (pinfunction "B_1") (pintype "passive"))
      (node (ref "RP2") (pin "5") (pinfunction "5_5") (pintype "passive"))
    )
    (net (code "126") (name "Net-(Q50-B)") (class "Default")
      (node (ref "Q50") (pin "1") (pinfunction "B_1") (pintype "passive"))
      (node (ref "RP5") (pin "8") (pinfunction "8_8") (pintype "passive"))
    )
    (net (code "127") (name "Net-(Q51-B)") (class "Default")
      (node (ref "Q51") (pin "1") (pinfunction "B_1") (pintype "passive"))
      (node (ref "RP5") (pin "7") (pinfunction "7_7") (pintype "passive"))
    )
    (net (code "128") (name "Net-(Q52-B)") (class "Default")
      (node (ref "Q52") (pin "1") (pinfunction "B_1") (pintype "passive"))
      (node (ref "RP5") (pin "6") (pinfunction "6_6") (pintype "passive"))
    )
    (net (code "129") (name "Net-(Q53-B)") (class "Default")
      (node (ref "Q53") (pin "1") (pinfunction "B_1") (pintype "passive"))
      (node (ref "RP5") (pin "5") (pinfunction "5_5") (pintype "passive"))
    )
    (net (code "130") (name "Net-(Q54-B)") (class "Default")
      (node (ref "Q54") (pin "1") (pinfunction "B_1") (pintype "passive"))
      (node (ref "RP6") (pin "8") (pinfunction "8_8") (pintype "passive"))
    )
    (net (code "131") (name "Net-(Q55-B)") (class "Default")
      (node (ref "Q55") (pin "1") (pinfunction "B_1") (pintype "passive"))
      (node (ref "RP6") (pin "7") (pinfunction "7_7") (pintype "passive"))
    )
    (net (code "132") (name "Net-(Q56-B)") (class "Default")
      (node (ref "Q56") (pin "1") (pinfunction "B_1") (pintype "passive"))
      (node (ref "RP6") (pin "6") (pinfunction "6_6") (pintype "passive"))
    )
    (net (code "133") (name "Net-(Q57-B)") (class "Default")
      (node (ref "Q57") (pin "1") (pinfunction "B_1") (pintype "passive"))
      (node (ref "RP6") (pin "5") (pinfunction "5_5") (pintype "passive"))
    )
    (net (code "134") (name "Net-(Q60-B)") (class "Default")
      (node (ref "Q60") (pin "1") (pinfunction "B_1") (pintype "passive"))
      (node (ref "RP9") (pin "8") (pinfunction "8_8") (pintype "passive"))
    )
    (net (code "135") (name "Net-(Q61-B)") (class "Default")
      (node (ref "Q61") (pin "1") (pinfunction "B_1") (pintype "passive"))
      (node (ref "RP9") (pin "7") (pinfunction "7_7") (pintype "passive"))
    )
    (net (code "136") (name "Net-(Q62-B)") (class "Default")
      (node (ref "Q62") (pin "1") (pinfunction "B_1") (pintype "passive"))
      (node (ref "RP9") (pin "6") (pinfunction "6_6") (pintype "passive"))
    )
    (net (code "137") (name "Net-(Q63-B)") (class "Default")
      (node (ref "Q63") (pin "1") (pinfunction "B_1") (pintype "passive"))
      (node (ref "RP9") (pin "5") (pinfunction "5_5") (pintype "passive"))
    )
    (net (code "138") (name "Net-(Q64-B)") (class "Default")
      (node (ref "Q64") (pin "1") (pinfunction "B_1") (pintype "passive"))
      (node (ref "RP10") (pin "8") (pinfunction "8_8") (pintype "passive"))
    )
    (net (code "139") (name "Net-(Q65-B)") (class "Default")
      (node (ref "Q65") (pin "1") (pinfunction "B_1") (pintype "passive"))
      (node (ref "RP10") (pin "7") (pinfunction "7_7") (pintype "passive"))
    )
    (net (code "140") (name "Net-(Q66-B)") (class "Default")
      (node (ref "Q66") (pin "1") (pinfunction "B_1") (pintype "passive"))
      (node (ref "RP10") (pin "6") (pinfunction "6_6") (pintype "passive"))
    )
    (net (code "141") (name "Net-(Q67-B)") (class "Default")
      (node (ref "Q67") (pin "1") (pinfunction "B_1") (pintype "passive"))
      (node (ref "RP10") (pin "5") (pinfunction "5_5") (pintype "passive"))
    )
    (net (code "142") (name "Net-(Q70-B)") (class "Default")
      (node (ref "Q70") (pin "1") (pinfunction "B_1") (pintype "passive"))
      (node (ref "RP13") (pin "8") (pinfunction "8_8") (pintype "passive"))
    )
    (net (code "143") (name "Net-(Q71-B)") (class "Default")
      (node (ref "Q71") (pin "1") (pinfunction "B_1") (pintype "passive"))
      (node (ref "RP13") (pin "7") (pinfunction "7_7") (pintype "passive"))
    )
    (net (code "144") (name "Net-(Q72-B)") (class "Default")
      (node (ref "Q72") (pin "1") (pinfunction "B_1") (pintype "passive"))
      (node (ref "RP13") (pin "6") (pinfunction "6_6") (pintype "passive"))
    )
    (net (code "145") (name "Net-(Q73-B)") (class "Default")
      (node (ref "Q73") (pin "1") (pinfunction "B_1") (pintype "passive"))
      (node (ref "RP13") (pin "5") (pinfunction "5_5") (pintype "passive"))
    )
    (net (code "146") (name "Net-(Q74-B)") (class "Default")
      (node (ref "Q74") (pin "1") (pinfunction "B_1") (pintype "passive"))
      (node (ref "RP14") (pin "8") (pinfunction "8_8") (pintype "passive"))
    )
    (net (code "147") (name "Net-(Q75-B)") (class "Default")
      (node (ref "Q75") (pin "1") (pinfunction "B_1") (pintype "passive"))
      (node (ref "RP14") (pin "7") (pinfunction "7_7") (pintype "passive"))
    )
    (net (code "148") (name "Net-(Q76-B)") (class "Default")
      (node (ref "Q76") (pin "1") (pinfunction "B_1") (pintype "passive"))
      (node (ref "RP14") (pin "6") (pinfunction "6_6") (pintype "passive"))
    )
    (net (code "149") (name "Net-(Q77-B)") (class "Default")
      (node (ref "Q77") (pin "1") (pinfunction "B_1") (pintype "passive"))
      (node (ref "RP14") (pin "5") (pinfunction "5_5") (pintype "passive"))
    )
  )
)
